# AUDIO.net
KiCad netlist of a schematic drawn in Altium Designer
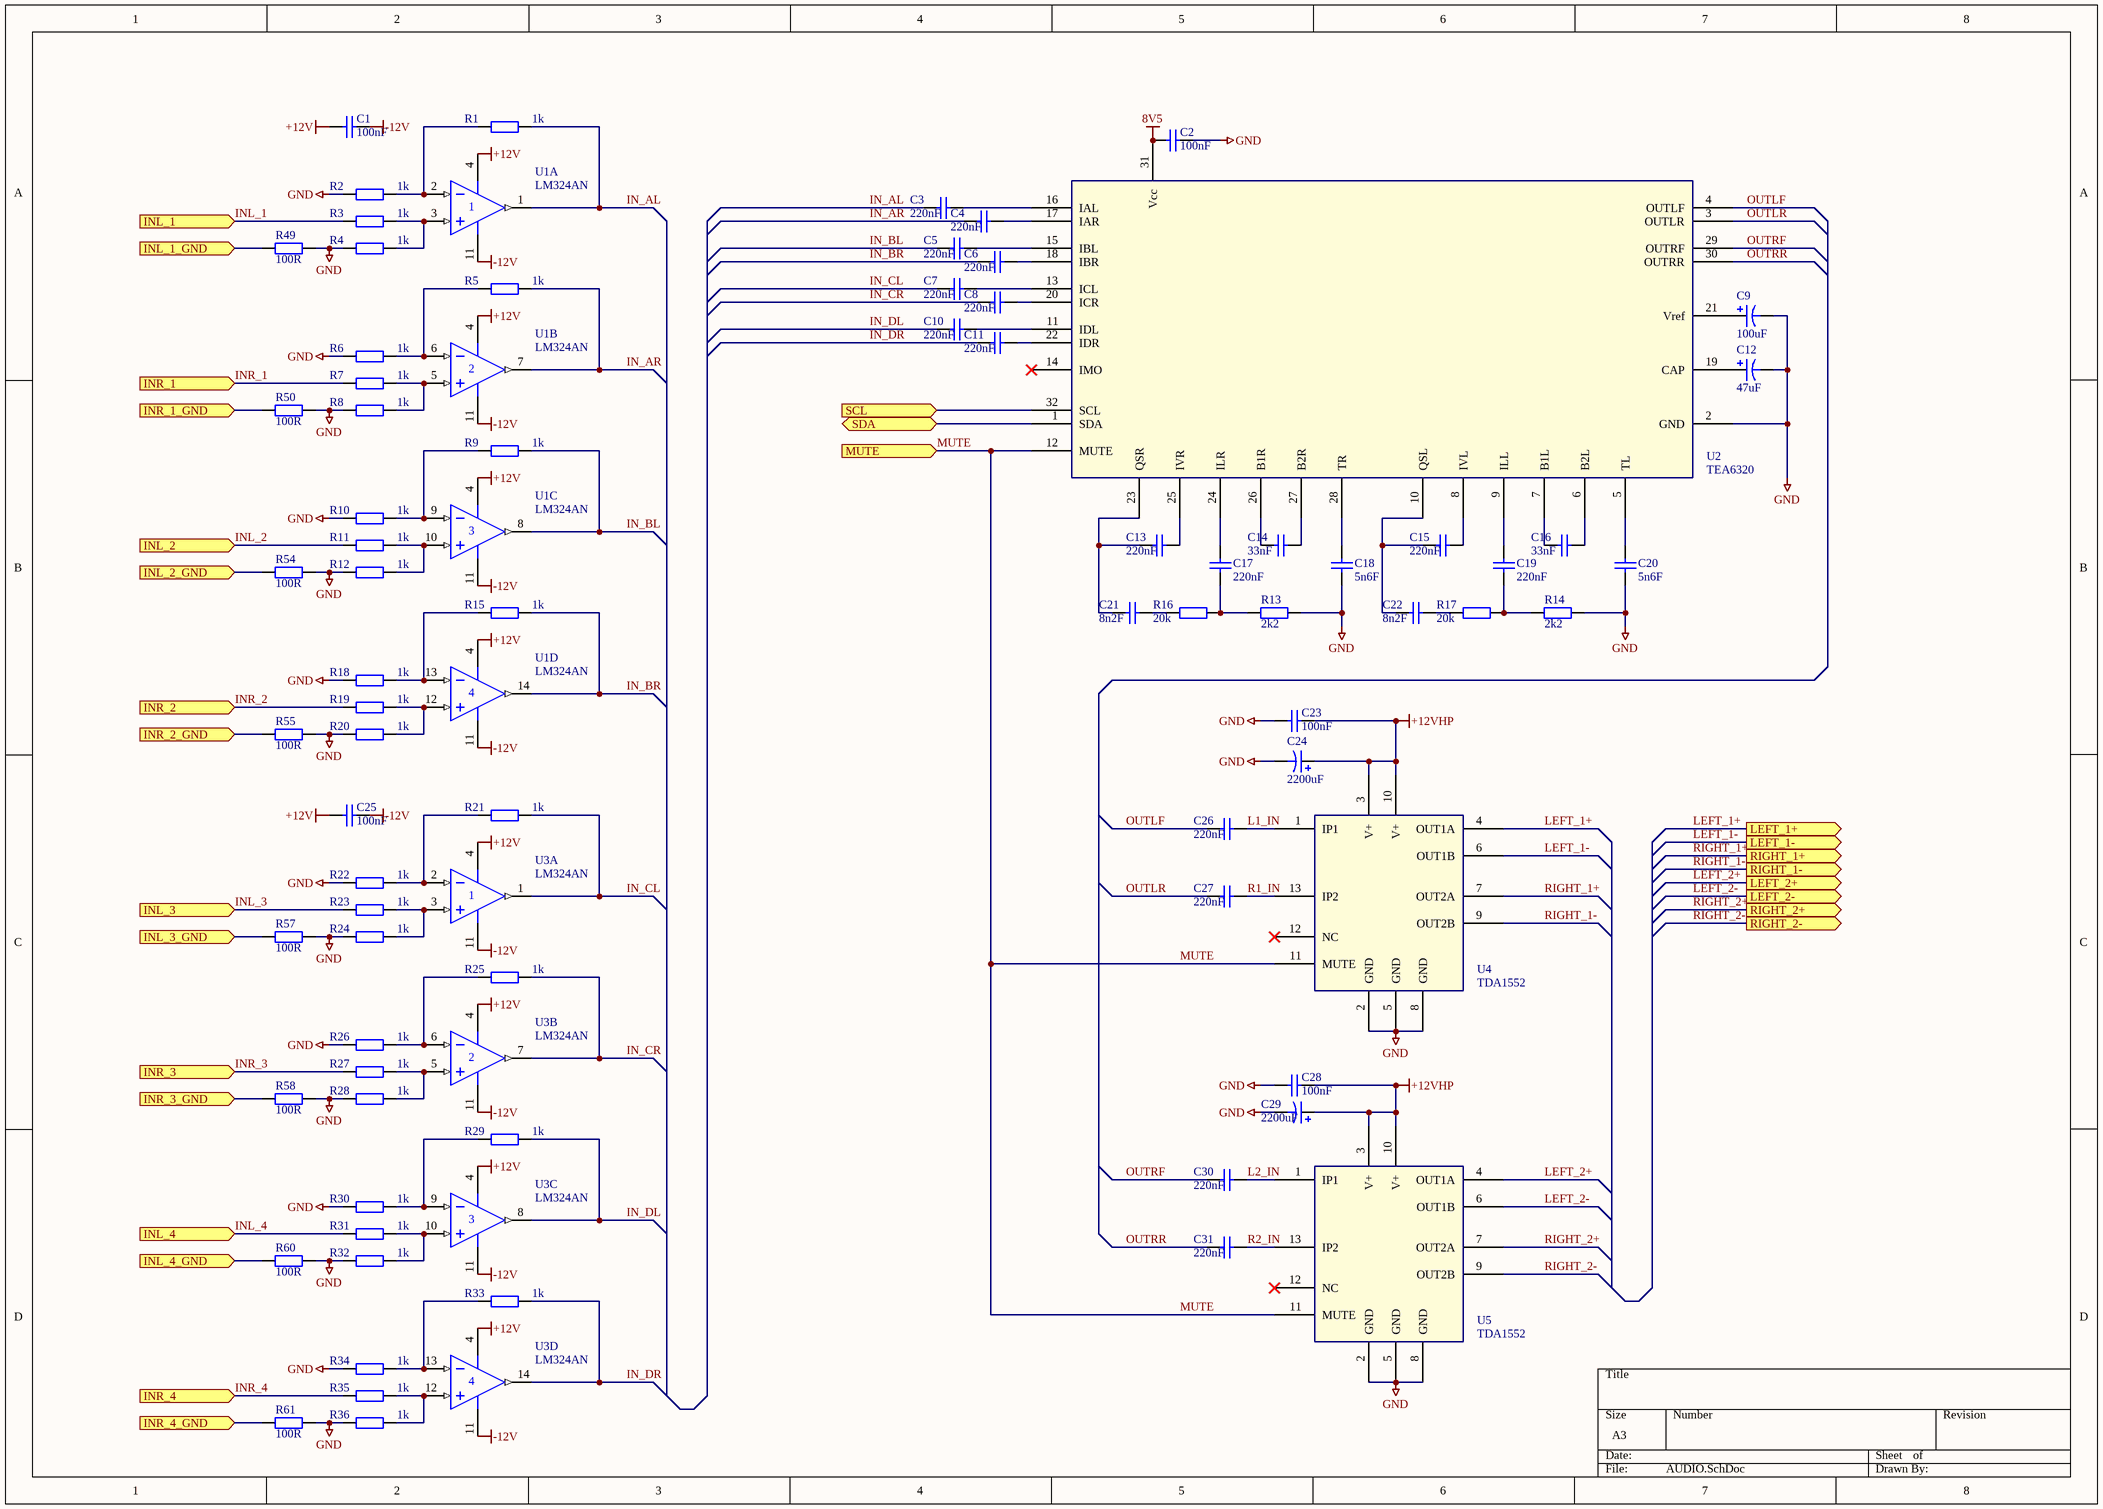
[diagram p0: AUDIO.SchDoc]

(export (version "E")
  (design (tool "Eeschema 10.0.6"))
  (components
    (comp (ref "C1")
      (value "100nF")
      (footprint "CAP (3D) - 0603")
      (description "Capacitor")
      (fields
        (field (name "MANUFACTURER") "YAEGO")
        (field (name "MANUFACTURER PART NO.") "CC0603ZRY5V9BB104")
      )
      (libsource (lib "Miscellaneous Devices") (part "Cap"))
    )
    (comp (ref "C2")
      (value "100nF")
      (footprint "CAP (3D) - 0603")
      (description "Capacitor")
      (fields
        (field (name "MANUFACTURER") "YAEGO")
        (field (name "MANUFACTURER PART NO.") "CC0603ZRY5V9BB104")
      )
      (libsource (lib "Miscellaneous Devices") (part "Cap"))
    )
    (comp (ref "C3")
      (value "220nF")
      (footprint "CAP (3D) - 0603")
      (description "Capacitor")
      (fields
        (field (name "MANUFACTURER") "YAGEO")
        (field (name "MANUFACTURER PART NO.") "CC0603KRX7R6BB224")
      )
      (libsource (lib "Miscellaneous Devices") (part "Cap"))
    )
    (comp (ref "C4")
      (value "220nF")
      (footprint "CAP (3D) - 0603")
      (description "Capacitor")
      (fields
        (field (name "MANUFACTURER") "YAGEO")
        (field (name "MANUFACTURER PART NO.") "CC0603KRX7R6BB224")
      )
      (libsource (lib "Miscellaneous Devices") (part "Cap"))
    )
    (comp (ref "C5")
      (value "220nF")
      (footprint "CAP (3D) - 0603")
      (description "Capacitor")
      (fields
        (field (name "MANUFACTURER") "YAGEO")
        (field (name "MANUFACTURER PART NO.") "CC0603KRX7R6BB224")
      )
      (libsource (lib "Miscellaneous Devices") (part "Cap"))
    )
    (comp (ref "C6")
      (value "220nF")
      (footprint "CAP (3D) - 0603")
      (description "Capacitor")
      (fields
        (field (name "MANUFACTURER") "YAGEO")
        (field (name "MANUFACTURER PART NO.") "CC0603KRX7R6BB224")
      )
      (libsource (lib "Miscellaneous Devices") (part "Cap"))
    )
    (comp (ref "C7")
      (value "220nF")
      (footprint "CAP (3D) - 0603")
      (description "Capacitor")
      (fields
        (field (name "MANUFACTURER") "YAGEO")
        (field (name "MANUFACTURER PART NO.") "CC0603KRX7R6BB224")
      )
      (libsource (lib "Miscellaneous Devices") (part "Cap"))
    )
    (comp (ref "C8")
      (value "220nF")
      (footprint "CAP (3D) - 0603")
      (description "Capacitor")
      (fields
        (field (name "MANUFACTURER") "YAGEO")
        (field (name "MANUFACTURER PART NO.") "CC0603KRX7R6BB224")
      )
      (libsource (lib "Miscellaneous Devices") (part "Cap"))
    )
    (comp (ref "C9")
      (value "100uF")
      (footprint "CAPPR5-5x5")
      (description "Polarized Capacitor (Radial)")
      (fields (field (name "MANUFACTURER") "EPCOS") (field (name "MANUFACTURER PART NO.") "B41828A7107M7"))
      (libsource (lib "Miscellaneous Devices") (part "Cap Pol1"))
    )
    (comp (ref "C10")
      (value "220nF")
      (footprint "CAP (3D) - 0603")
      (description "Capacitor")
      (fields
        (field (name "MANUFACTURER") "YAGEO")
        (field (name "MANUFACTURER PART NO.") "CC0603KRX7R6BB224")
      )
      (libsource (lib "Miscellaneous Devices") (part "Cap"))
    )
    (comp (ref "C11")
      (value "220nF")
      (footprint "CAP (3D) - 0603")
      (description "Capacitor")
      (fields
        (field (name "MANUFACTURER") "YAGEO")
        (field (name "MANUFACTURER PART NO.") "CC0603KRX7R6BB224")
      )
      (libsource (lib "Miscellaneous Devices") (part "Cap"))
    )
    (comp (ref "C12")
      (value "47uF")
      (footprint "CAPPR5-5x5")
      (description "Polarized Capacitor (Radial)")
      (fields (field (name "MANUFACTURER") "EPCOS") (field (name "MANUFACTURER PART NO.") "B41821A7476M000"))
      (libsource (lib "Miscellaneous Devices") (part "Cap Pol1"))
    )
    (comp (ref "C13")
      (value "220nF")
      (footprint "CAP (3D) - 0603")
      (description "Capacitor")
      (fields
        (field (name "MANUFACTURER") "YAGEO")
        (field (name "MANUFACTURER PART NO.") "CC0603KRX7R6BB224")
      )
      (libsource (lib "Miscellaneous Devices") (part "Cap"))
    )
    (comp (ref "C14")
      (value "33nF")
      (footprint "CAP (3D) - 0603")
      (description "Capacitor")
      (fields
        (field (name "MANUFACTURER") "VISHAY")
        (field (name "MANUFACTURER PART NO.") "VJ0603Y333KXACW1BC")
      )
      (libsource (lib "Miscellaneous Devices") (part "Cap"))
    )
    (comp (ref "C15")
      (value "220nF")
      (footprint "CAP (3D) - 0603")
      (description "Capacitor")
      (fields
        (field (name "MANUFACTURER") "YAGEO")
        (field (name "MANUFACTURER PART NO.") "CC0603KRX7R6BB224")
      )
      (libsource (lib "Miscellaneous Devices") (part "Cap"))
    )
    (comp (ref "C16")
      (value "33nF")
      (footprint "CAP (3D) - 0603")
      (description "Capacitor")
      (fields
        (field (name "MANUFACTURER") "VISHAY")
        (field (name "MANUFACTURER PART NO.") "VJ0603Y333KXACW1BC")
      )
      (libsource (lib "Miscellaneous Devices") (part "Cap"))
    )
    (comp (ref "C17")
      (value "220nF")
      (footprint "CAP (3D) - 0603")
      (description "Capacitor")
      (fields
        (field (name "MANUFACTURER") "YAGEO")
        (field (name "MANUFACTURER PART NO.") "CC0603KRX7R6BB224")
      )
      (libsource (lib "Miscellaneous Devices") (part "Cap"))
    )
    (comp (ref "C18")
      (value "5n6F")
      (footprint "CAP (3D) - 0603")
      (description "Capacitor")
      (fields
        (field (name "MANUFACTURER") "YAEGO")
        (field (name "MANUFACTURER PART NO.") "CC0603KRX7R9BB562")
      )
      (libsource (lib "Miscellaneous Devices") (part "Cap"))
    )
    (comp (ref "C19")
      (value "220nF")
      (footprint "CAP (3D) - 0603")
      (description "Capacitor")
      (fields
        (field (name "MANUFACTURER") "YAGEO")
        (field (name "MANUFACTURER PART NO.") "CC0603KRX7R6BB224")
      )
      (libsource (lib "Miscellaneous Devices") (part "Cap"))
    )
    (comp (ref "C20")
      (value "5n6F")
      (footprint "CAP (3D) - 0603")
      (description "Capacitor")
      (fields
        (field (name "MANUFACTURER") "YAEGO")
        (field (name "MANUFACTURER PART NO.") "CC0603KRX7R9BB562")
      )
      (libsource (lib "Miscellaneous Devices") (part "Cap"))
    )
    (comp (ref "C21")
      (value "8n2F")
      (footprint "CAP (3D) - 0603")
      (description "Capacitor")
      (fields
        (field (name "MANUFACTURER") "VISHAY")
        (field (name "MANUFACTURER PART NO.") "VJ0603Y822KXACW1BC")
      )
      (libsource (lib "Miscellaneous Devices") (part "Cap"))
    )
    (comp (ref "C22")
      (value "8n2F")
      (footprint "CAP (3D) - 0603")
      (description "Capacitor")
      (fields
        (field (name "MANUFACTURER") "VISHAY")
        (field (name "MANUFACTURER PART NO.") "VJ0603Y822KXACW1BC")
      )
      (libsource (lib "Miscellaneous Devices") (part "Cap"))
    )
    (comp (ref "C23")
      (value "100nF")
      (footprint "CAP (3D) - 0603")
      (description "Capacitor")
      (fields
        (field (name "MANUFACTURER") "YAEGO")
        (field (name "MANUFACTURER PART NO.") "CC0603ZRY5V9BB104")
      )
      (libsource (lib "Miscellaneous Devices") (part "Cap"))
    )
    (comp (ref "C24")
      (value "2200uF")
      (footprint "CAPPR7.5-16x35")
      (description "Polarized Capacitor (Radial)")
      (fields
        (field (name "MANUFACTURER") "Lelon")
        (field (name "MANUFACTURER PART NO.") "RGA222M1EBK-1625P")
      )
      (libsource (lib "Miscellaneous Devices") (part "Cap Pol1"))
    )
    (comp (ref "C25")
      (value "100nF")
      (footprint "CAP (3D) - 0603")
      (description "Capacitor")
      (fields
        (field (name "MANUFACTURER") "YAEGO")
        (field (name "MANUFACTURER PART NO.") "CC0603ZRY5V9BB104")
      )
      (libsource (lib "Miscellaneous Devices") (part "Cap"))
    )
    (comp (ref "C26")
      (value "220nF")
      (footprint "CAP (3D) - 0603")
      (description "Capacitor")
      (fields
        (field (name "MANUFACTURER") "YAGEO")
        (field (name "MANUFACTURER PART NO.") "CC0603KRX7R6BB224")
      )
      (libsource (lib "Miscellaneous Devices") (part "Cap"))
    )
    (comp (ref "C27")
      (value "220nF")
      (footprint "CAP (3D) - 0603")
      (description "Capacitor")
      (fields
        (field (name "MANUFACTURER") "YAGEO")
        (field (name "MANUFACTURER PART NO.") "CC0603KRX7R6BB224")
      )
      (libsource (lib "Miscellaneous Devices") (part "Cap"))
    )
    (comp (ref "C28")
      (value "100nF")
      (footprint "CAP (3D) - 0603")
      (description "Capacitor")
      (fields
        (field (name "MANUFACTURER") "YAEGO")
        (field (name "MANUFACTURER PART NO.") "CC0603ZRY5V9BB104")
      )
      (libsource (lib "Miscellaneous Devices") (part "Cap"))
    )
    (comp (ref "C29")
      (value "2200uF")
      (footprint "CAPPR7.5-16x35")
      (description "Polarized Capacitor (Radial)")
      (fields
        (field (name "MANUFACTURER") "Lelon")
        (field (name "MANUFACTURER PART NO.") "RGA222M1EBK-1625P")
      )
      (libsource (lib "Miscellaneous Devices") (part "Cap Pol1"))
    )
    (comp (ref "C30")
      (value "220nF")
      (footprint "CAP (3D) - 0603")
      (description "Capacitor")
      (fields
        (field (name "MANUFACTURER") "YAGEO")
        (field (name "MANUFACTURER PART NO.") "CC0603KRX7R6BB224")
      )
      (libsource (lib "Miscellaneous Devices") (part "Cap"))
    )
    (comp (ref "C31")
      (value "220nF")
      (footprint "CAP (3D) - 0603")
      (description "Capacitor")
      (fields
        (field (name "MANUFACTURER") "YAGEO")
        (field (name "MANUFACTURER PART NO.") "CC0603KRX7R6BB224")
      )
      (libsource (lib "Miscellaneous Devices") (part "Cap"))
    )
    (comp (ref "R1")
      (value "1k")
      (footprint "RES (3D) - 0603")
      (description "Resistor")
      (fields (field (name "MANUFACTURER") "YAEGO") (field (name "MANUFACTURER PART NO.") "AC0603FR-071KL"))
      (libsource (lib "Miscellaneous Devices") (part "Res2"))
    )
    (comp (ref "R2")
      (value "1k")
      (footprint "RES (3D) - 0603")
      (description "Resistor")
      (fields (field (name "MANUFACTURER") "YAEGO") (field (name "MANUFACTURER PART NO.") "AC0603FR-071KL"))
      (libsource (lib "Miscellaneous Devices") (part "Res2"))
    )
    (comp (ref "R3")
      (value "1k")
      (footprint "RES (3D) - 0603")
      (description "Resistor")
      (fields (field (name "MANUFACTURER") "YAEGO") (field (name "MANUFACTURER PART NO.") "AC0603FR-071KL"))
      (libsource (lib "Miscellaneous Devices") (part "Res2"))
    )
    (comp (ref "R4")
      (value "1k")
      (footprint "RES (3D) - 0603")
      (description "Resistor")
      (fields (field (name "MANUFACTURER") "YAEGO") (field (name "MANUFACTURER PART NO.") "AC0603FR-071KL"))
      (libsource (lib "Miscellaneous Devices") (part "Res2"))
    )
    (comp (ref "R5")
      (value "1k")
      (footprint "RES (3D) - 0603")
      (description "Resistor")
      (fields (field (name "MANUFACTURER") "YAEGO") (field (name "MANUFACTURER PART NO.") "AC0603FR-071KL"))
      (libsource (lib "Miscellaneous Devices") (part "Res2"))
    )
    (comp (ref "R6")
      (value "1k")
      (footprint "RES (3D) - 0603")
      (description "Resistor")
      (fields (field (name "MANUFACTURER") "YAEGO") (field (name "MANUFACTURER PART NO.") "AC0603FR-071KL"))
      (libsource (lib "Miscellaneous Devices") (part "Res2"))
    )
    (comp (ref "R7")
      (value "1k")
      (footprint "RES (3D) - 0603")
      (description "Resistor")
      (fields (field (name "MANUFACTURER") "YAEGO") (field (name "MANUFACTURER PART NO.") "AC0603FR-071KL"))
      (libsource (lib "Miscellaneous Devices") (part "Res2"))
    )
    (comp (ref "R8")
      (value "1k")
      (footprint "RES (3D) - 0603")
      (description "Resistor")
      (fields (field (name "MANUFACTURER") "YAEGO") (field (name "MANUFACTURER PART NO.") "AC0603FR-071KL"))
      (libsource (lib "Miscellaneous Devices") (part "Res2"))
    )
    (comp (ref "R9")
      (value "1k")
      (footprint "RES (3D) - 0603")
      (description "Resistor")
      (fields (field (name "MANUFACTURER") "YAEGO") (field (name "MANUFACTURER PART NO.") "AC0603FR-071KL"))
      (libsource (lib "Miscellaneous Devices") (part "Res2"))
    )
    (comp (ref "R10")
      (value "1k")
      (footprint "RES (3D) - 0603")
      (description "Resistor")
      (fields (field (name "MANUFACTURER") "YAEGO") (field (name "MANUFACTURER PART NO.") "AC0603FR-071KL"))
      (libsource (lib "Miscellaneous Devices") (part "Res2"))
    )
    (comp (ref "R11")
      (value "1k")
      (footprint "RES (3D) - 0603")
      (description "Resistor")
      (fields (field (name "MANUFACTURER") "YAEGO") (field (name "MANUFACTURER PART NO.") "AC0603FR-071KL"))
      (libsource (lib "Miscellaneous Devices") (part "Res2"))
    )
    (comp (ref "R12")
      (value "1k")
      (footprint "RES (3D) - 0603")
      (description "Resistor")
      (fields (field (name "MANUFACTURER") "YAEGO") (field (name "MANUFACTURER PART NO.") "AC0603FR-071KL"))
      (libsource (lib "Miscellaneous Devices") (part "Res2"))
    )
    (comp (ref "R13")
      (value "2k2")
      (footprint "RES (3D) - 0603")
      (description "Resistor")
      (fields (field (name "MANUFACTURER") "YAEGO") (field (name "MANUFACTURER PART NO.") "RC0603JR-072K2L"))
      (libsource (lib "Miscellaneous Devices") (part "Res2"))
    )
    (comp (ref "R14")
      (value "2k2")
      (footprint "RES (3D) - 0603")
      (description "Resistor")
      (fields (field (name "MANUFACTURER") "YAEGO") (field (name "MANUFACTURER PART NO.") "RC0603JR-072K2L"))
      (libsource (lib "Miscellaneous Devices") (part "Res2"))
    )
    (comp (ref "R15")
      (value "1k")
      (footprint "RES (3D) - 0603")
      (description "Resistor")
      (fields (field (name "MANUFACTURER") "YAEGO") (field (name "MANUFACTURER PART NO.") "AC0603FR-071KL"))
      (libsource (lib "Miscellaneous Devices") (part "Res2"))
    )
    (comp (ref "R16")
      (value "20k")
      (footprint "RES (3D) - 0603")
      (description "Resistor")
      (fields (field (name "MANUFACTURER") "XICON") (field (name "MANUFACTURER PART NO.") "302-20K-RC"))
      (libsource (lib "") (part "Res2_1"))
    )
    (comp (ref "R17")
      (value "20k")
      (footprint "RES (3D) - 0603")
      (description "Resistor")
      (fields (field (name "MANUFACTURER") "XICON") (field (name "MANUFACTURER PART NO.") "302-20K-RC"))
      (libsource (lib "") (part "Res2_1"))
    )
    (comp (ref "R18")
      (value "1k")
      (footprint "RES (3D) - 0603")
      (description "Resistor")
      (fields (field (name "MANUFACTURER") "YAEGO") (field (name "MANUFACTURER PART NO.") "AC0603FR-071KL"))
      (libsource (lib "Miscellaneous Devices") (part "Res2"))
    )
    (comp (ref "R19")
      (value "1k")
      (footprint "RES (3D) - 0603")
      (description "Resistor")
      (fields (field (name "MANUFACTURER") "YAEGO") (field (name "MANUFACTURER PART NO.") "AC0603FR-071KL"))
      (libsource (lib "Miscellaneous Devices") (part "Res2"))
    )
    (comp (ref "R20")
      (value "1k")
      (footprint "RES (3D) - 0603")
      (description "Resistor")
      (fields (field (name "MANUFACTURER") "YAEGO") (field (name "MANUFACTURER PART NO.") "AC0603FR-071KL"))
      (libsource (lib "Miscellaneous Devices") (part "Res2"))
    )
    (comp (ref "R21")
      (value "1k")
      (footprint "RES (3D) - 0603")
      (description "Resistor")
      (fields (field (name "MANUFACTURER") "YAEGO") (field (name "MANUFACTURER PART NO.") "AC0603FR-071KL"))
      (libsource (lib "Miscellaneous Devices") (part "Res2"))
    )
    (comp (ref "R22")
      (value "1k")
      (footprint "RES (3D) - 0603")
      (description "Resistor")
      (fields (field (name "MANUFACTURER") "YAEGO") (field (name "MANUFACTURER PART NO.") "AC0603FR-071KL"))
      (libsource (lib "Miscellaneous Devices") (part "Res2"))
    )
    (comp (ref "R23")
      (value "1k")
      (footprint "RES (3D) - 0603")
      (description "Resistor")
      (fields (field (name "MANUFACTURER") "YAEGO") (field (name "MANUFACTURER PART NO.") "AC0603FR-071KL"))
      (libsource (lib "Miscellaneous Devices") (part "Res2"))
    )
    (comp (ref "R24")
      (value "1k")
      (footprint "RES (3D) - 0603")
      (description "Resistor")
      (fields (field (name "MANUFACTURER") "YAEGO") (field (name "MANUFACTURER PART NO.") "AC0603FR-071KL"))
      (libsource (lib "Miscellaneous Devices") (part "Res2"))
    )
    (comp (ref "R25")
      (value "1k")
      (footprint "RES (3D) - 0603")
      (description "Resistor")
      (fields (field (name "MANUFACTURER") "YAEGO") (field (name "MANUFACTURER PART NO.") "AC0603FR-071KL"))
      (libsource (lib "Miscellaneous Devices") (part "Res2"))
    )
    (comp (ref "R26")
      (value "1k")
      (footprint "RES (3D) - 0603")
      (description "Resistor")
      (fields (field (name "MANUFACTURER") "YAEGO") (field (name "MANUFACTURER PART NO.") "AC0603FR-071KL"))
      (libsource (lib "Miscellaneous Devices") (part "Res2"))
    )
    (comp (ref "R27")
      (value "1k")
      (footprint "RES (3D) - 0603")
      (description "Resistor")
      (fields (field (name "MANUFACTURER") "YAEGO") (field (name "MANUFACTURER PART NO.") "AC0603FR-071KL"))
      (libsource (lib "Miscellaneous Devices") (part "Res2"))
    )
    (comp (ref "R28")
      (value "1k")
      (footprint "RES (3D) - 0603")
      (description "Resistor")
      (fields (field (name "MANUFACTURER") "YAEGO") (field (name "MANUFACTURER PART NO.") "AC0603FR-071KL"))
      (libsource (lib "Miscellaneous Devices") (part "Res2"))
    )
    (comp (ref "R29")
      (value "1k")
      (footprint "RES (3D) - 0603")
      (description "Resistor")
      (fields (field (name "MANUFACTURER") "YAEGO") (field (name "MANUFACTURER PART NO.") "AC0603FR-071KL"))
      (libsource (lib "Miscellaneous Devices") (part "Res2"))
    )
    (comp (ref "R30")
      (value "1k")
      (footprint "RES (3D) - 0603")
      (description "Resistor")
      (fields (field (name "MANUFACTURER") "YAEGO") (field (name "MANUFACTURER PART NO.") "AC0603FR-071KL"))
      (libsource (lib "Miscellaneous Devices") (part "Res2"))
    )
    (comp (ref "R31")
      (value "1k")
      (footprint "RES (3D) - 0603")
      (description "Resistor")
      (fields (field (name "MANUFACTURER") "YAEGO") (field (name "MANUFACTURER PART NO.") "AC0603FR-071KL"))
      (libsource (lib "Miscellaneous Devices") (part "Res2"))
    )
    (comp (ref "R32")
      (value "1k")
      (footprint "RES (3D) - 0603")
      (description "Resistor")
      (fields (field (name "MANUFACTURER") "YAEGO") (field (name "MANUFACTURER PART NO.") "AC0603FR-071KL"))
      (libsource (lib "Miscellaneous Devices") (part "Res2"))
    )
    (comp (ref "R33")
      (value "1k")
      (footprint "RES (3D) - 0603")
      (description "Resistor")
      (fields (field (name "MANUFACTURER") "YAEGO") (field (name "MANUFACTURER PART NO.") "AC0603FR-071KL"))
      (libsource (lib "Miscellaneous Devices") (part "Res2"))
    )
    (comp (ref "R34")
      (value "1k")
      (footprint "RES (3D) - 0603")
      (description "Resistor")
      (fields (field (name "MANUFACTURER") "YAEGO") (field (name "MANUFACTURER PART NO.") "AC0603FR-071KL"))
      (libsource (lib "Miscellaneous Devices") (part "Res2"))
    )
    (comp (ref "R35")
      (value "1k")
      (footprint "RES (3D) - 0603")
      (description "Resistor")
      (fields (field (name "MANUFACTURER") "YAEGO") (field (name "MANUFACTURER PART NO.") "AC0603FR-071KL"))
      (libsource (lib "Miscellaneous Devices") (part "Res2"))
    )
    (comp (ref "R36")
      (value "1k")
      (footprint "RES (3D) - 0603")
      (description "Resistor")
      (fields (field (name "MANUFACTURER") "YAEGO") (field (name "MANUFACTURER PART NO.") "AC0603FR-071KL"))
      (libsource (lib "Miscellaneous Devices") (part "Res2"))
    )
    (comp (ref "R49")
      (value "100R")
      (footprint "RES (3D) - 0603")
      (description "Resistor")
      (fields (field (name "MANUFACTURER") "YAEGO") (field (name "MANUFACTURER PART NO.") "RC0603FR-07100RL"))
      (libsource (lib "Miscellaneous Devices") (part "Res2"))
    )
    (comp (ref "R50")
      (value "100R")
      (footprint "RES (3D) - 0603")
      (description "Resistor")
      (fields (field (name "MANUFACTURER") "YAEGO") (field (name "MANUFACTURER PART NO.") "RC0603FR-07100RL"))
      (libsource (lib "Miscellaneous Devices") (part "Res2"))
    )
    (comp (ref "R54")
      (value "100R")
      (footprint "RES (3D) - 0603")
      (description "Resistor")
      (fields (field (name "MANUFACTURER") "YAEGO") (field (name "MANUFACTURER PART NO.") "RC0603FR-07100RL"))
      (libsource (lib "Miscellaneous Devices") (part "Res2"))
    )
    (comp (ref "R55")
      (value "100R")
      (footprint "RES (3D) - 0603")
      (description "Resistor")
      (fields (field (name "MANUFACTURER") "YAEGO") (field (name "MANUFACTURER PART NO.") "RC0603FR-07100RL"))
      (libsource (lib "Miscellaneous Devices") (part "Res2"))
    )
    (comp (ref "R57")
      (value "100R")
      (footprint "RES (3D) - 0603")
      (description "Resistor")
      (fields (field (name "MANUFACTURER") "YAEGO") (field (name "MANUFACTURER PART NO.") "RC0603FR-07100RL"))
      (libsource (lib "Miscellaneous Devices") (part "Res2"))
    )
    (comp (ref "R58")
      (value "100R")
      (footprint "RES (3D) - 0603")
      (description "Resistor")
      (fields (field (name "MANUFACTURER") "YAEGO") (field (name "MANUFACTURER PART NO.") "RC0603FR-07100RL"))
      (libsource (lib "Miscellaneous Devices") (part "Res2"))
    )
    (comp (ref "R60")
      (value "100R")
      (footprint "RES (3D) - 0603")
      (description "Resistor")
      (fields (field (name "MANUFACTURER") "YAEGO") (field (name "MANUFACTURER PART NO.") "RC0603FR-07100RL"))
      (libsource (lib "Miscellaneous Devices") (part "Res2"))
    )
    (comp (ref "R61")
      (value "100R")
      (footprint "RES (3D) - 0603")
      (description "Resistor")
      (fields (field (name "MANUFACTURER") "YAEGO") (field (name "MANUFACTURER PART NO.") "RC0603FR-07100RL"))
      (libsource (lib "Miscellaneous Devices") (part "Res2"))
    )
    (comp (ref "U1")
      (value "LM324AN")
      (footprint "N014")
      (description "Quadruple Operational Amplifier")
      (fields (field (name "MANUFACTURER") "ST MICRO") (field (name "MOUSER PART NO.") "511-LM324AN"))
      (libsource (lib "TI Operational Amplifier") (part "LM324AN"))
    )
    (comp (ref "U2")
      (value "TEA6320")
      (footprint "SOIC127P1047-32L")
      (description "TEA6320 SOUND FADER CONTROL")
      (fields
        (field (name "MANUFACTURER") "NXP SEMICONDUCTOR")
        (field (name "MANUFACTURER PART NO.") "TEA6320T/V1,518")
      )
      (libsource (lib "Distribution Amp") (part "TEA6320"))
    )
    (comp (ref "U3")
      (value "LM324AN")
      (footprint "N014")
      (description "Quadruple Operational Amplifier")
      (fields (field (name "MANUFACTURER") "ST MICRO") (field (name "MOUSER PART NO.") "511-LM324AN"))
      (libsource (lib "TI Operational Amplifier") (part "LM324AN"))
    )
    (comp (ref "U4")
      (value "TDA1552")
      (footprint "DBS13P")
      (fields
        (field (name "MANUFACTURER") "NXP SEMICONDUCTOR")
        (field (name "MANUFACTURER PART NO.") "TDA1552Q/N4,112")
        (field (name "MOUSER PART NO.") "771-TDA1552QU")
      )
      (libsource (lib "Distribution Amp") (part "TDA1552"))
    )
    (comp (ref "U5")
      (value "TDA1552")
      (footprint "DBS13P")
      (fields
        (field (name "MANUFACTURER") "NXP SEMICONDUCTOR")
        (field (name "MANUFACTURER PART NO.") "TDA1552Q/N4,112")
        (field (name "MOUSER PART NO.") "771-TDA1552QU")
      )
      (libsource (lib "Distribution Amp") (part "TDA1552"))
    )
  )
  (nets
    (net (code "1") (name "+12V") (class "Default")
      (node (ref "C1") (pin "1") (pinfunction "1_1") (pintype "passive"))
      (node (ref "C25") (pin "1") (pinfunction "1_1") (pintype "passive"))
      (node (ref "U1") (pin "4") (pinfunction "V+_4") (pintype "power_in"))
      (node (ref "U3") (pin "4") (pinfunction "V+_4") (pintype "power_in"))
    )
    (net (code "2") (name "+12VHP") (class "Default")
      (node (ref "C23") (pin "2") (pinfunction "2_2") (pintype "passive"))
      (node (ref "C24") (pin "1") (pinfunction "1_1") (pintype "passive"))
      (node (ref "C28") (pin "2") (pinfunction "2_2") (pintype "passive"))
      (node (ref "C29") (pin "1") (pinfunction "1_1") (pintype "passive"))
      (node (ref "U4") (pin "10") (pinfunction "V+_10") (pintype "passive"))
      (node (ref "U4") (pin "3") (pinfunction "V+_3") (pintype "passive"))
      (node (ref "U5") (pin "10") (pinfunction "V+_10") (pintype "passive"))
      (node (ref "U5") (pin "3") (pinfunction "V+_3") (pintype "passive"))
    )
    (net (code "3") (name "-12V") (class "Default")
      (node (ref "C1") (pin "2") (pinfunction "2_2") (pintype "passive"))
      (node (ref "C25") (pin "2") (pinfunction "2_2") (pintype "passive"))
      (node (ref "U1") (pin "11") (pinfunction "V-_11") (pintype "power_in"))
      (node (ref "U3") (pin "11") (pinfunction "V-_11") (pintype "power_in"))
    )
    (net (code "4") (name "/INL_1") (class "Default")
      (node (ref "R3") (pin "1") (pinfunction "1_1") (pintype "passive"))
    )
    (net (code "5") (name "/INL_1_GND") (class "Default")
      (node (ref "R49") (pin "1") (pinfunction "1_1") (pintype "passive"))
    )
    (net (code "6") (name "/INL_2") (class "Default")
      (node (ref "R11") (pin "1") (pinfunction "1_1") (pintype "passive"))
    )
    (net (code "7") (name "/INL_2_GND") (class "Default")
      (node (ref "R54") (pin "1") (pinfunction "1_1") (pintype "passive"))
    )
    (net (code "8") (name "/INL_3") (class "Default")
      (node (ref "R23") (pin "1") (pinfunction "1_1") (pintype "passive"))
    )
    (net (code "9") (name "/INL_3_GND") (class "Default")
      (node (ref "R57") (pin "1") (pinfunction "1_1") (pintype "passive"))
    )
    (net (code "10") (name "/INL_4") (class "Default")
      (node (ref "R31") (pin "1") (pinfunction "1_1") (pintype "passive"))
    )
    (net (code "11") (name "/INL_4_GND") (class "Default")
      (node (ref "R60") (pin "1") (pinfunction "1_1") (pintype "passive"))
    )
    (net (code "12") (name "/INR_1") (class "Default")
      (node (ref "R7") (pin "1") (pinfunction "1_1") (pintype "passive"))
    )
    (net (code "13") (name "/INR_1_GND") (class "Default")
      (node (ref "R50") (pin "1") (pinfunction "1_1") (pintype "passive"))
    )
    (net (code "14") (name "/INR_2") (class "Default")
      (node (ref "R19") (pin "1") (pinfunction "1_1") (pintype "passive"))
    )
    (net (code "15") (name "/INR_2_GND") (class "Default")
      (node (ref "R55") (pin "1") (pinfunction "1_1") (pintype "passive"))
    )
    (net (code "16") (name "/INR_3") (class "Default")
      (node (ref "R27") (pin "1") (pinfunction "1_1") (pintype "passive"))
    )
    (net (code "17") (name "/INR_3_GND") (class "Default")
      (node (ref "R58") (pin "1") (pinfunction "1_1") (pintype "passive"))
    )
    (net (code "18") (name "/INR_4") (class "Default")
      (node (ref "R35") (pin "1") (pinfunction "1_1") (pintype "passive"))
    )
    (net (code "19") (name "/INR_4_GND") (class "Default")
      (node (ref "R61") (pin "1") (pinfunction "1_1") (pintype "passive"))
    )
    (net (code "20") (name "/IN_AL") (class "Default")
      (node (ref "C3") (pin "1") (pinfunction "1_1") (pintype "passive"))
      (node (ref "R1") (pin "2") (pinfunction "2_2") (pintype "passive"))
      (node (ref "U1") (pin "1") (pinfunction "OUT_1") (pintype "output"))
    )
    (net (code "21") (name "/IN_AR") (class "Default")
      (node (ref "C4") (pin "1") (pinfunction "1_1") (pintype "passive"))
      (node (ref "R5") (pin "2") (pinfunction "2_2") (pintype "passive"))
      (node (ref "U1") (pin "7") (pinfunction "OUT_7") (pintype "output"))
    )
    (net (code "22") (name "/IN_BL") (class "Default")
      (node (ref "C5") (pin "1") (pinfunction "1_1") (pintype "passive"))
      (node (ref "R9") (pin "2") (pinfunction "2_2") (pintype "passive"))
      (node (ref "U1") (pin "8") (pinfunction "OUT_8") (pintype "output"))
    )
    (net (code "23") (name "/IN_BR") (class "Default")
      (node (ref "C6") (pin "1") (pinfunction "1_1") (pintype "passive"))
      (node (ref "R15") (pin "2") (pinfunction "2_2") (pintype "passive"))
      (node (ref "U1") (pin "14") (pinfunction "OUT_14") (pintype "output"))
    )
    (net (code "24") (name "/IN_CL") (class "Default")
      (node (ref "C7") (pin "1") (pinfunction "1_1") (pintype "passive"))
      (node (ref "R21") (pin "2") (pinfunction "2_2") (pintype "passive"))
      (node (ref "U3") (pin "1") (pinfunction "OUT_1") (pintype "output"))
    )
    (net (code "25") (name "/IN_CR") (class "Default")
      (node (ref "C8") (pin "1") (pinfunction "1_1") (pintype "passive"))
      (node (ref "R25") (pin "2") (pinfunction "2_2") (pintype "passive"))
      (node (ref "U3") (pin "7") (pinfunction "OUT_7") (pintype "output"))
    )
    (net (code "26") (name "/IN_DL") (class "Default")
      (node (ref "C10") (pin "1") (pinfunction "1_1") (pintype "passive"))
      (node (ref "R29") (pin "2") (pinfunction "2_2") (pintype "passive"))
      (node (ref "U3") (pin "8") (pinfunction "OUT_8") (pintype "output"))
    )
    (net (code "27") (name "/IN_DR") (class "Default")
      (node (ref "C11") (pin "1") (pinfunction "1_1") (pintype "passive"))
      (node (ref "R33") (pin "2") (pinfunction "2_2") (pintype "passive"))
      (node (ref "U3") (pin "14") (pinfunction "OUT_14") (pintype "output"))
    )
    (net (code "28") (name "/L1_IN") (class "Default")
      (node (ref "C26") (pin "2") (pinfunction "2_2") (pintype "passive"))
      (node (ref "U4") (pin "1") (pinfunction "IP1_1") (pintype "passive"))
    )
    (net (code "29") (name "/L2_IN") (class "Default")
      (node (ref "C30") (pin "2") (pinfunction "2_2") (pintype "passive"))
      (node (ref "U5") (pin "1") (pinfunction "IP1_1") (pintype "passive"))
    )
    (net (code "30") (name "/LEFT_1+") (class "Default")
      (node (ref "U4") (pin "4") (pinfunction "OUT1A_4") (pintype "passive"))
    )
    (net (code "31") (name "/LEFT_1-") (class "Default")
      (node (ref "U4") (pin "6") (pinfunction "OUT1B_6") (pintype "passive"))
    )
    (net (code "32") (name "/LEFT_2+") (class "Default")
      (node (ref "U5") (pin "4") (pinfunction "OUT1A_4") (pintype "passive"))
    )
    (net (code "33") (name "/LEFT_2-") (class "Default")
      (node (ref "U5") (pin "6") (pinfunction "OUT1B_6") (pintype "passive"))
    )
    (net (code "34") (name "/MUTE") (class "Default")
      (node (ref "U2") (pin "12") (pinfunction "MUTE_12") (pintype "passive"))
      (node (ref "U4") (pin "11") (pinfunction "MUTE_11") (pintype "passive"))
      (node (ref "U5") (pin "11") (pinfunction "MUTE_11") (pintype "passive"))
    )
    (net (code "35") (name "/OUTLF") (class "Default")
      (node (ref "C26") (pin "1") (pinfunction "1_1") (pintype "passive"))
      (node (ref "U2") (pin "4") (pinfunction "OUTLF_4") (pintype "passive"))
    )
    (net (code "36") (name "/OUTLR") (class "Default")
      (node (ref "C27") (pin "1") (pinfunction "1_1") (pintype "passive"))
      (node (ref "U2") (pin "3") (pinfunction "OUTLR_3") (pintype "passive"))
    )
    (net (code "37") (name "/OUTRF") (class "Default")
      (node (ref "C30") (pin "1") (pinfunction "1_1") (pintype "passive"))
      (node (ref "U2") (pin "29") (pinfunction "OUTRF_29") (pintype "passive"))
    )
    (net (code "38") (name "/OUTRR") (class "Default")
      (node (ref "C31") (pin "1") (pinfunction "1_1") (pintype "passive"))
      (node (ref "U2") (pin "30") (pinfunction "OUTRR_30") (pintype "passive"))
    )
    (net (code "39") (name "/R1_IN") (class "Default")
      (node (ref "C27") (pin "2") (pinfunction "2_2") (pintype "passive"))
      (node (ref "U4") (pin "13") (pinfunction "IP2_13") (pintype "passive"))
    )
    (net (code "40") (name "/R2_IN") (class "Default")
      (node (ref "C31") (pin "2") (pinfunction "2_2") (pintype "passive"))
      (node (ref "U5") (pin "13") (pinfunction "IP2_13") (pintype "passive"))
    )
    (net (code "41") (name "/RIGHT_1+") (class "Default")
      (node (ref "U4") (pin "7") (pinfunction "OUT2A_7") (pintype "passive"))
    )
    (net (code "42") (name "/RIGHT_1-") (class "Default")
      (node (ref "U4") (pin "9") (pinfunction "OUT2B_9") (pintype "passive"))
    )
    (net (code "43") (name "/RIGHT_2+") (class "Default")
      (node (ref "U5") (pin "7") (pinfunction "OUT2A_7") (pintype "passive"))
    )
    (net (code "44") (name "/RIGHT_2-") (class "Default")
      (node (ref "U5") (pin "9") (pinfunction "OUT2B_9") (pintype "passive"))
    )
    (net (code "45") (name "/SCL") (class "Default")
      (node (ref "U2") (pin "32") (pinfunction "SCL_32") (pintype "passive"))
    )
    (net (code "46") (name "/SDA") (class "Default")
      (node (ref "U2") (pin "1") (pinfunction "SDA_1") (pintype "passive"))
    )
    (net (code "47") (name "8V5") (class "Default")
      (node (ref "C2") (pin "1") (pinfunction "1_1") (pintype "passive"))
      (node (ref "U2") (pin "31") (pinfunction "Vcc_31") (pintype "passive"))
    )
    (net (code "48") (name "GND") (class "Default")
      (node (ref "C12") (pin "2") (pinfunction "2_2") (pintype "passive"))
      (node (ref "C18") (pin "2") (pinfunction "2_2") (pintype "passive"))
      (node (ref "C2") (pin "2") (pinfunction "2_2") (pintype "passive"))
      (node (ref "C20") (pin "2") (pinfunction "2_2") (pintype "passive"))
      (node (ref "C23") (pin "1") (pinfunction "1_1") (pintype "passive"))
      (node (ref "C24") (pin "2") (pinfunction "2_2") (pintype "passive"))
      (node (ref "C28") (pin "1") (pinfunction "1_1") (pintype "passive"))
      (node (ref "C29") (pin "2") (pinfunction "2_2") (pintype "passive"))
      (node (ref "C9") (pin "2") (pinfunction "2_2") (pintype "passive"))
      (node (ref "R10") (pin "1") (pinfunction "1_1") (pintype "passive"))
      (node (ref "R12") (pin "1") (pinfunction "1_1") (pintype "passive"))
      (node (ref "R13") (pin "2") (pinfunction "2_2") (pintype "passive"))
      (node (ref "R14") (pin "2") (pinfunction "2_2") (pintype "passive"))
      (node (ref "R18") (pin "1") (pinfunction "1_1") (pintype "passive"))
      (node (ref "R2") (pin "1") (pinfunction "1_1") (pintype "passive"))
      (node (ref "R20") (pin "1") (pinfunction "1_1") (pintype "passive"))
      (node (ref "R22") (pin "1") (pinfunction "1_1") (pintype "passive"))
      (node (ref "R24") (pin "1") (pinfunction "1_1") (pintype "passive"))
      (node (ref "R26") (pin "1") (pinfunction "1_1") (pintype "passive"))
      (node (ref "R28") (pin "1") (pinfunction "1_1") (pintype "passive"))
      (node (ref "R30") (pin "1") (pinfunction "1_1") (pintype "passive"))
      (node (ref "R32") (pin "1") (pinfunction "1_1") (pintype "passive"))
      (node (ref "R34") (pin "1") (pinfunction "1_1") (pintype "passive"))
      (node (ref "R36") (pin "1") (pinfunction "1_1") (pintype "passive"))
      (node (ref "R4") (pin "1") (pinfunction "1_1") (pintype "passive"))
      (node (ref "R49") (pin "2") (pinfunction "2_2") (pintype "passive"))
      (node (ref "R50") (pin "2") (pinfunction "2_2") (pintype "passive"))
      (node (ref "R54") (pin "2") (pinfunction "2_2") (pintype "passive"))
      (node (ref "R55") (pin "2") (pinfunction "2_2") (pintype "passive"))
      (node (ref "R57") (pin "2") (pinfunction "2_2") (pintype "passive"))
      (node (ref "R58") (pin "2") (pinfunction "2_2") (pintype "passive"))
      (node (ref "R6") (pin "1") (pinfunction "1_1") (pintype "passive"))
      (node (ref "R60") (pin "2") (pinfunction "2_2") (pintype "passive"))
      (node (ref "R61") (pin "2") (pinfunction "2_2") (pintype "passive"))
      (node (ref "R8") (pin "1") (pinfunction "1_1") (pintype "passive"))
      (node (ref "U2") (pin "2") (pinfunction "GND_2") (pintype "passive"))
      (node (ref "U4") (pin "2") (pinfunction "GND_2") (pintype "passive"))
      (node (ref "U4") (pin "5") (pinfunction "GND_5") (pintype "passive"))
      (node (ref "U4") (pin "8") (pinfunction "GND_8") (pintype "passive"))
      (node (ref "U5") (pin "2") (pinfunction "GND_2") (pintype "passive"))
      (node (ref "U5") (pin "5") (pinfunction "GND_5") (pintype "passive"))
      (node (ref "U5") (pin "8") (pinfunction "GND_8") (pintype "passive"))
    )
    (net (code "49") (name "Net-(C17-Pad2)") (class "Default")
      (node (ref "C17") (pin "2") (pinfunction "2_2") (pintype "passive"))
      (node (ref "R13") (pin "1") (pinfunction "1_1") (pintype "passive"))
      (node (ref "R16") (pin "1") (pinfunction "1_1") (pintype "passive"))
    )
    (net (code "50") (name "Net-(C19-Pad2)") (class "Default")
      (node (ref "C19") (pin "2") (pinfunction "2_2") (pintype "passive"))
      (node (ref "R14") (pin "1") (pinfunction "1_1") (pintype "passive"))
      (node (ref "R17") (pin "1") (pinfunction "1_1") (pintype "passive"))
    )
    (net (code "51") (name "Net-(C21-Pad2)") (class "Default")
      (node (ref "C21") (pin "2") (pinfunction "2_2") (pintype "passive"))
      (node (ref "R16") (pin "2") (pinfunction "2_2") (pintype "passive"))
    )
    (net (code "52") (name "Net-(C22-Pad2)") (class "Default")
      (node (ref "C22") (pin "2") (pinfunction "2_2") (pintype "passive"))
      (node (ref "R17") (pin "2") (pinfunction "2_2") (pintype "passive"))
    )
    (net (code "53") (name "Net-(U1A-IN+)") (class "Default")
      (node (ref "R3") (pin "2") (pinfunction "2_2") (pintype "passive"))
      (node (ref "R4") (pin "2") (pinfunction "2_2") (pintype "passive"))
      (node (ref "U1") (pin "3") (pinfunction "IN+_3") (pintype "input"))
    )
    (net (code "54") (name "Net-(U1A-IN-)") (class "Default")
      (node (ref "R1") (pin "1") (pinfunction "1_1") (pintype "passive"))
      (node (ref "R2") (pin "2") (pinfunction "2_2") (pintype "passive"))
      (node (ref "U1") (pin "2") (pinfunction "IN-_2") (pintype "input"))
    )
    (net (code "55") (name "Net-(U1B-IN+)") (class "Default")
      (node (ref "R7") (pin "2") (pinfunction "2_2") (pintype "passive"))
      (node (ref "R8") (pin "2") (pinfunction "2_2") (pintype "passive"))
      (node (ref "U1") (pin "5") (pinfunction "IN+_5") (pintype "input"))
    )
    (net (code "56") (name "Net-(U1B-IN-)") (class "Default")
      (node (ref "R5") (pin "1") (pinfunction "1_1") (pintype "passive"))
      (node (ref "R6") (pin "2") (pinfunction "2_2") (pintype "passive"))
      (node (ref "U1") (pin "6") (pinfunction "IN-_6") (pintype "input"))
    )
    (net (code "57") (name "Net-(U1C-IN+)") (class "Default")
      (node (ref "R11") (pin "2") (pinfunction "2_2") (pintype "passive"))
      (node (ref "R12") (pin "2") (pinfunction "2_2") (pintype "passive"))
      (node (ref "U1") (pin "10") (pinfunction "IN+_10") (pintype "input"))
    )
    (net (code "58") (name "Net-(U1C-IN-)") (class "Default")
      (node (ref "R10") (pin "2") (pinfunction "2_2") (pintype "passive"))
      (node (ref "R9") (pin "1") (pinfunction "1_1") (pintype "passive"))
      (node (ref "U1") (pin "9") (pinfunction "IN-_9") (pintype "input"))
    )
    (net (code "59") (name "Net-(U1D-IN+)") (class "Default")
      (node (ref "R19") (pin "2") (pinfunction "2_2") (pintype "passive"))
      (node (ref "R20") (pin "2") (pinfunction "2_2") (pintype "passive"))
      (node (ref "U1") (pin "12") (pinfunction "IN+_12") (pintype "input"))
    )
    (net (code "60") (name "Net-(U1D-IN-)") (class "Default")
      (node (ref "R15") (pin "1") (pinfunction "1_1") (pintype "passive"))
      (node (ref "R18") (pin "2") (pinfunction "2_2") (pintype "passive"))
      (node (ref "U1") (pin "13") (pinfunction "IN-_13") (pintype "input"))
    )
    (net (code "61") (name "Net-(U2-B1L)") (class "Default")
      (node (ref "C16") (pin "1") (pinfunction "1_1") (pintype "passive"))
      (node (ref "U2") (pin "7") (pinfunction "B1L_7") (pintype "passive"))
    )
    (net (code "62") (name "Net-(U2-B1R)") (class "Default")
      (node (ref "C14") (pin "1") (pinfunction "1_1") (pintype "passive"))
      (node (ref "U2") (pin "26") (pinfunction "B1R_26") (pintype "passive"))
    )
    (net (code "63") (name "Net-(U2-B2L)") (class "Default")
      (node (ref "C16") (pin "2") (pinfunction "2_2") (pintype "passive"))
      (node (ref "U2") (pin "6") (pinfunction "B2L_6") (pintype "passive"))
    )
    (net (code "64") (name "Net-(U2-B2R)") (class "Default")
      (node (ref "C14") (pin "2") (pinfunction "2_2") (pintype "passive"))
      (node (ref "U2") (pin "27") (pinfunction "B2R_27") (pintype "passive"))
    )
    (net (code "65") (name "Net-(U2-CAP)") (class "Default")
      (node (ref "C12") (pin "1") (pinfunction "1_1") (pintype "passive"))
      (node (ref "U2") (pin "19") (pinfunction "CAP_19") (pintype "passive"))
    )
    (net (code "66") (name "Net-(U2-IAL)") (class "Default")
      (node (ref "C3") (pin "2") (pinfunction "2_2") (pintype "passive"))
      (node (ref "U2") (pin "16") (pinfunction "IAL_16") (pintype "passive"))
    )
    (net (code "67") (name "Net-(U2-IAR)") (class "Default")
      (node (ref "C4") (pin "2") (pinfunction "2_2") (pintype "passive"))
      (node (ref "U2") (pin "17") (pinfunction "IAR_17") (pintype "passive"))
    )
    (net (code "68") (name "Net-(U2-IBL)") (class "Default")
      (node (ref "C5") (pin "2") (pinfunction "2_2") (pintype "passive"))
      (node (ref "U2") (pin "15") (pinfunction "IBL_15") (pintype "passive"))
    )
    (net (code "69") (name "Net-(U2-IBR)") (class "Default")
      (node (ref "C6") (pin "2") (pinfunction "2_2") (pintype "passive"))
      (node (ref "U2") (pin "18") (pinfunction "IBR_18") (pintype "passive"))
    )
    (net (code "70") (name "Net-(U2-ICL)") (class "Default")
      (node (ref "C7") (pin "2") (pinfunction "2_2") (pintype "passive"))
      (node (ref "U2") (pin "13") (pinfunction "ICL_13") (pintype "passive"))
    )
    (net (code "71") (name "Net-(U2-ICR)") (class "Default")
      (node (ref "C8") (pin "2") (pinfunction "2_2") (pintype "passive"))
      (node (ref "U2") (pin "20") (pinfunction "ICR_20") (pintype "passive"))
    )
    (net (code "72") (name "Net-(U2-IDL)") (class "Default")
      (node (ref "C10") (pin "2") (pinfunction "2_2") (pintype "passive"))
      (node (ref "U2") (pin "11") (pinfunction "IDL_11") (pintype "passive"))
    )
    (net (code "73") (name "Net-(U2-IDR)") (class "Default")
      (node (ref "C11") (pin "2") (pinfunction "2_2") (pintype "passive"))
      (node (ref "U2") (pin "22") (pinfunction "IDR_22") (pintype "passive"))
    )
    (net (code "74") (name "Net-(U2-ILL)") (class "Default")
      (node (ref "C19") (pin "1") (pinfunction "1_1") (pintype "passive"))
      (node (ref "U2") (pin "9") (pinfunction "ILL_9") (pintype "passive"))
    )
    (net (code "75") (name "Net-(U2-ILR)") (class "Default")
      (node (ref "C17") (pin "1") (pinfunction "1_1") (pintype "passive"))
      (node (ref "U2") (pin "24") (pinfunction "ILR_24") (pintype "passive"))
    )
    (net (code "76") (name "Net-(U2-IVL)") (class "Default")
      (node (ref "C15") (pin "2") (pinfunction "2_2") (pintype "passive"))
      (node (ref "U2") (pin "8") (pinfunction "IVL_8") (pintype "passive"))
    )
    (net (code "77") (name "Net-(U2-IVR)") (class "Default")
      (node (ref "C13") (pin "2") (pinfunction "2_2") (pintype "passive"))
      (node (ref "U2") (pin "25") (pinfunction "IVR_25") (pintype "passive"))
    )
    (net (code "78") (name "Net-(U2-QSL)") (class "Default")
      (node (ref "C15") (pin "1") (pinfunction "1_1") (pintype "passive"))
      (node (ref "C22") (pin "1") (pinfunction "1_1") (pintype "passive"))
      (node (ref "U2") (pin "10") (pinfunction "QSL_10") (pintype "passive"))
    )
    (net (code "79") (name "Net-(U2-QSR)") (class "Default")
      (node (ref "C13") (pin "1") (pinfunction "1_1") (pintype "passive"))
      (node (ref "C21") (pin "1") (pinfunction "1_1") (pintype "passive"))
      (node (ref "U2") (pin "23") (pinfunction "QSR_23") (pintype "passive"))
    )
    (net (code "80") (name "Net-(U2-TL)") (class "Default")
      (node (ref "C20") (pin "1") (pinfunction "1_1") (pintype "passive"))
      (node (ref "U2") (pin "5") (pinfunction "TL_5") (pintype "passive"))
    )
    (net (code "81") (name "Net-(U2-TR)") (class "Default")
      (node (ref "C18") (pin "1") (pinfunction "1_1") (pintype "passive"))
      (node (ref "U2") (pin "28") (pinfunction "TR_28") (pintype "passive"))
    )
    (net (code "82") (name "Net-(U2-Vref)") (class "Default")
      (node (ref "C9") (pin "1") (pinfunction "1_1") (pintype "passive"))
      (node (ref "U2") (pin "21") (pinfunction "Vref_21") (pintype "passive"))
    )
    (net (code "83") (name "Net-(U3A-IN+)") (class "Default")
      (node (ref "R23") (pin "2") (pinfunction "2_2") (pintype "passive"))
      (node (ref "R24") (pin "2") (pinfunction "2_2") (pintype "passive"))
      (node (ref "U3") (pin "3") (pinfunction "IN+_3") (pintype "input"))
    )
    (net (code "84") (name "Net-(U3A-IN-)") (class "Default")
      (node (ref "R21") (pin "1") (pinfunction "1_1") (pintype "passive"))
      (node (ref "R22") (pin "2") (pinfunction "2_2") (pintype "passive"))
      (node (ref "U3") (pin "2") (pinfunction "IN-_2") (pintype "input"))
    )
    (net (code "85") (name "Net-(U3B-IN+)") (class "Default")
      (node (ref "R27") (pin "2") (pinfunction "2_2") (pintype "passive"))
      (node (ref "R28") (pin "2") (pinfunction "2_2") (pintype "passive"))
      (node (ref "U3") (pin "5") (pinfunction "IN+_5") (pintype "input"))
    )
    (net (code "86") (name "Net-(U3B-IN-)") (class "Default")
      (node (ref "R25") (pin "1") (pinfunction "1_1") (pintype "passive"))
      (node (ref "R26") (pin "2") (pinfunction "2_2") (pintype "passive"))
      (node (ref "U3") (pin "6") (pinfunction "IN-_6") (pintype "input"))
    )
    (net (code "87") (name "Net-(U3C-IN+)") (class "Default")
      (node (ref "R31") (pin "2") (pinfunction "2_2") (pintype "passive"))
      (node (ref "R32") (pin "2") (pinfunction "2_2") (pintype "passive"))
      (node (ref "U3") (pin "10") (pinfunction "IN+_10") (pintype "input"))
    )
    (net (code "88") (name "Net-(U3C-IN-)") (class "Default")
      (node (ref "R29") (pin "1") (pinfunction "1_1") (pintype "passive"))
      (node (ref "R30") (pin "2") (pinfunction "2_2") (pintype "passive"))
      (node (ref "U3") (pin "9") (pinfunction "IN-_9") (pintype "input"))
    )
    (net (code "89") (name "Net-(U3D-IN+)") (class "Default")
      (node (ref "R35") (pin "2") (pinfunction "2_2") (pintype "passive"))
      (node (ref "R36") (pin "2") (pinfunction "2_2") (pintype "passive"))
      (node (ref "U3") (pin "12") (pinfunction "IN+_12") (pintype "input"))
    )
    (net (code "90") (name "Net-(U3D-IN-)") (class "Default")
      (node (ref "R33") (pin "1") (pinfunction "1_1") (pintype "passive"))
      (node (ref "R34") (pin "2") (pinfunction "2_2") (pintype "passive"))
      (node (ref "U3") (pin "13") (pinfunction "IN-_13") (pintype "input"))
    )
    (net (code "91") (name "unconnected-(U2-IMO-Pad14)") (class "Default")
      (node (ref "U2") (pin "14") (pinfunction "IMO_14") (pintype "passive+no_connect"))
    )
    (net (code "92") (name "unconnected-(U4-NC-Pad12)") (class "Default")
      (node (ref "U4") (pin "12") (pinfunction "NC_12") (pintype "passive+no_connect"))
    )
    (net (code "93") (name "unconnected-(U5-NC-Pad12)") (class "Default")
      (node (ref "U5") (pin "12") (pinfunction "NC_12") (pintype "passive+no_connect"))
    )
  )
)
